# stonyman-imager-board.net
KiCad netlist of a schematic drawn in EAGLE
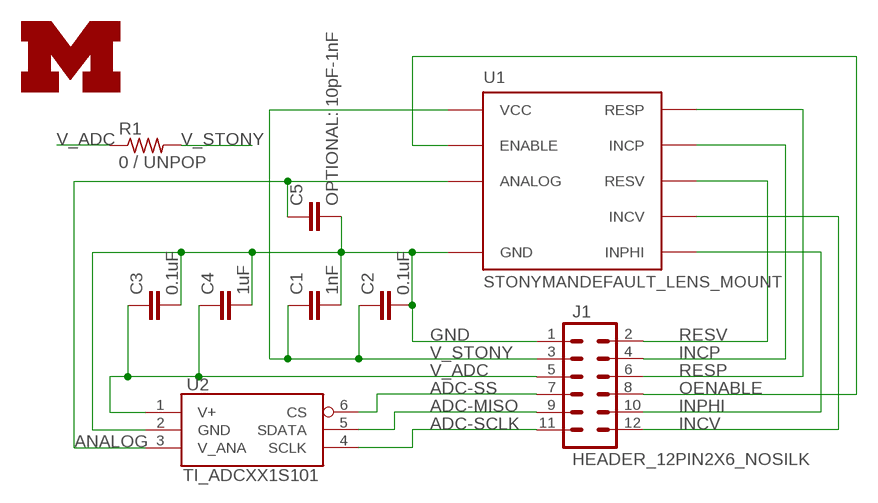
[diagram p0: schematic, sheet 1]

(export (version "E")
  (design (tool "Eeschema 10.0.6"))
  (components
    (comp (ref "C1")
      (value "1nF")
      (footprint "eagle-import:C0603")
      (libsource (lib "eagle-import") (part "C-EUC0603"))
    )
    (comp (ref "C2")
      (value "0.1uF")
      (footprint "eagle-import:C0603")
      (libsource (lib "eagle-import") (part "C-EUC0603"))
    )
    (comp (ref "C3")
      (value "0.1uF")
      (footprint "eagle-import:C0603")
      (libsource (lib "eagle-import") (part "C-EUC0603"))
    )
    (comp (ref "C4")
      (value "1uF")
      (footprint "eagle-import:C0603")
      (libsource (lib "eagle-import") (part "C-EUC0603"))
    )
    (comp (ref "C5")
      (value "OPTIONAL: 10pF-1nF")
      (footprint "eagle-import:C0603")
      (libsource (lib "eagle-import") (part "C-EUC0603"))
    )
    (comp (ref "J1")
      (value "HEADER_12PIN2X6_NOSILK")
      (footprint "eagle-import:HEADER2X6_0.05IN_NO_SILK")
      (libsource (lib "eagle-import") (part "HEADER_12PIN2X6_NOSILK"))
    )
    (comp (ref "R1")
      (value "0 / UNPOP")
      (footprint "eagle-import:R0603")
      (libsource (lib "eagle-import") (part "R-US_R0603"))
    )
    (comp (ref "U$1")
      (value "UMICH_SOLID_SMALL")
      (footprint "eagle-import:UMICH_SOLID_75MIL")
      (libsource (lib "eagle-import") (part "UMICH_SOLID_SMALL"))
    )
    (comp (ref "U1")
      (value "STONYMANDEFAULT_LENS_MOUNT")
      (footprint "eagle-import:STONYMAN_DEFAULT_LENS")
      (libsource (lib "eagle-import") (part "STONYMANDEFAULT_LENS_MOUNT"))
    )
    (comp (ref "U2")
      (value "TI_ADCXX1S101")
      (footprint "eagle-import:SOT23-6")
      (libsource (lib "eagle-import") (part "TI_ADCXX1S101"))
    )
  )
  (nets
    (net (code "1") (name "/ADC-MISO") (class "Default")
      (node (ref "J1") (pin "9") (pinfunction "9_9") (pintype "passive"))
      (node (ref "U2") (pin "5") (pinfunction "SDATA_5") (pintype "bidirectional"))
    )
    (net (code "2") (name "/ADC-SCLK") (class "Default")
      (node (ref "J1") (pin "11") (pinfunction "11_11") (pintype "passive"))
      (node (ref "U2") (pin "4") (pinfunction "SCLK_4") (pintype "bidirectional"))
    )
    (net (code "3") (name "/ADC-SS") (class "Default")
      (node (ref "J1") (pin "7") (pinfunction "7_7") (pintype "passive"))
      (node (ref "U2") (pin "6") (pinfunction "CS_6") (pintype "bidirectional"))
    )
    (net (code "4") (name "/ANALOG") (class "Default")
      (node (ref "C5") (pin "1") (pinfunction "1_1") (pintype "passive"))
      (node (ref "U1") (pin "P$8") (pinfunction "ANALOG_P$8") (pintype "output"))
      (node (ref "U2") (pin "3") (pinfunction "V_ANA_3") (pintype "bidirectional"))
    )
    (net (code "5") (name "/GND") (class "Default")
      (node (ref "C1") (pin "2") (pinfunction "2_2") (pintype "passive"))
      (node (ref "C2") (pin "2") (pinfunction "2_2") (pintype "passive"))
      (node (ref "C3") (pin "2") (pinfunction "2_2") (pintype "passive"))
      (node (ref "C4") (pin "2") (pinfunction "2_2") (pintype "passive"))
      (node (ref "C5") (pin "2") (pinfunction "2_2") (pintype "passive"))
      (node (ref "J1") (pin "1") (pinfunction "1_1") (pintype "passive"))
      (node (ref "U1") (pin "P$1") (pinfunction "GND_P$1") (pintype "power_in"))
      (node (ref "U1") (pin "P$10") (pinfunction "GND_P$10") (pintype "power_in"))
      (node (ref "U2") (pin "2") (pinfunction "GND_2") (pintype "bidirectional"))
    )
    (net (code "6") (name "/INCP") (class "Default")
      (node (ref "J1") (pin "4") (pinfunction "4_4") (pintype "passive"))
      (node (ref "U1") (pin "P$4") (pinfunction "INCP_P$4") (pintype "input"))
    )
    (net (code "7") (name "/INCV") (class "Default")
      (node (ref "J1") (pin "12") (pinfunction "12_12") (pintype "passive"))
      (node (ref "U1") (pin "P$6") (pinfunction "INCV_P$6") (pintype "input"))
    )
    (net (code "8") (name "/INPHI") (class "Default")
      (node (ref "J1") (pin "10") (pinfunction "10_10") (pintype "passive"))
      (node (ref "U1") (pin "P$7") (pinfunction "INPHI_P$7") (pintype "input"))
    )
    (net (code "9") (name "/OENABLE") (class "Default")
      (node (ref "J1") (pin "8") (pinfunction "8_8") (pintype "passive"))
      (node (ref "U1") (pin "P$9") (pinfunction "ENABLE_P$9") (pintype "input"))
    )
    (net (code "10") (name "/RESP") (class "Default")
      (node (ref "J1") (pin "6") (pinfunction "6_6") (pintype "passive"))
      (node (ref "U1") (pin "P$3") (pinfunction "RESP_P$3") (pintype "input"))
    )
    (net (code "11") (name "/RESV") (class "Default")
      (node (ref "J1") (pin "2") (pinfunction "2_2") (pintype "passive"))
      (node (ref "U1") (pin "P$5") (pinfunction "RESV_P$5") (pintype "input"))
    )
    (net (code "12") (name "/V_ADC") (class "Default")
      (node (ref "C3") (pin "1") (pinfunction "1_1") (pintype "passive"))
      (node (ref "C4") (pin "1") (pinfunction "1_1") (pintype "passive"))
      (node (ref "J1") (pin "5") (pinfunction "5_5") (pintype "passive"))
      (node (ref "R1") (pin "1") (pinfunction "1_1") (pintype "passive"))
      (node (ref "U2") (pin "1") (pinfunction "V+_1") (pintype "bidirectional"))
    )
    (net (code "13") (name "/V_STONY") (class "Default")
      (node (ref "C1") (pin "1") (pinfunction "1_1") (pintype "passive"))
      (node (ref "C2") (pin "1") (pinfunction "1_1") (pintype "passive"))
      (node (ref "J1") (pin "3") (pinfunction "3_3") (pintype "passive"))
      (node (ref "R1") (pin "2") (pinfunction "2_2") (pintype "passive"))
      (node (ref "U1") (pin "P$2") (pinfunction "VCC_P$2") (pintype "power_in"))
    )
  )
)
